# DeviceControl.net
KiCad netlist of a schematic drawn in Altium Designer
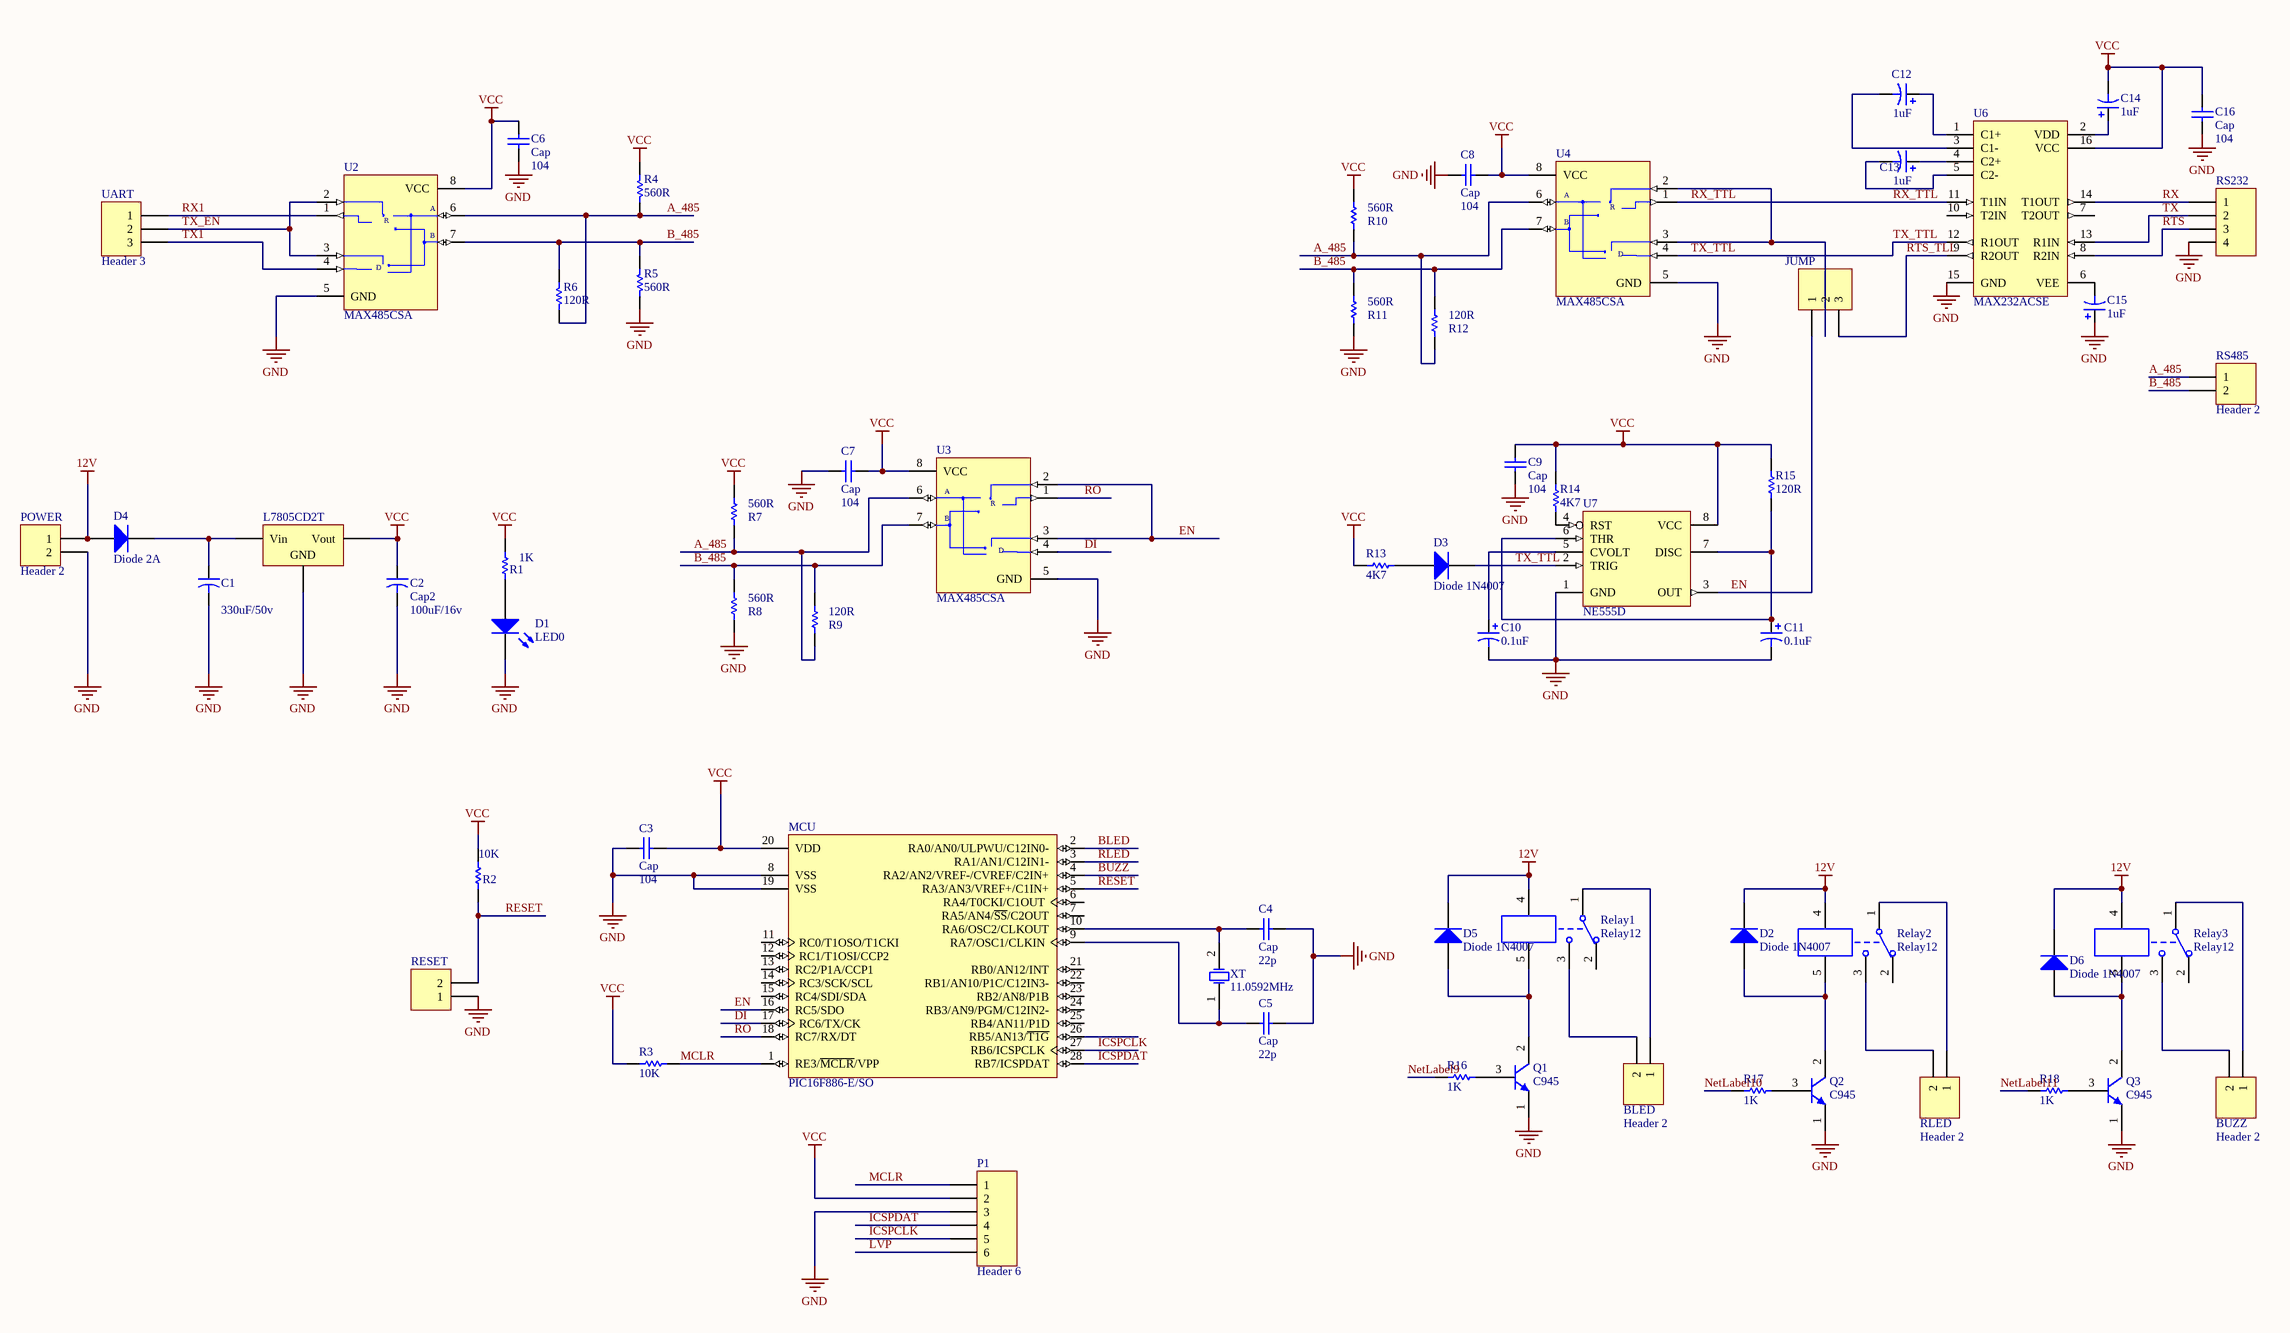
[diagram p0: DeviceControl.SchDoc]

(export (version "E")
  (design (tool "Eeschema 10.0.6"))
  (components
    (comp (ref "BLED")
      (value "Header 2")
      (footprint "Device:Header2 - duplicate")
      (description "Header, 2-Pin")
      (fields (field (name "PUBLISHER") "Altium Limited"))
      (libsource (lib "Miscellaneous Connectors") (part "Header 2"))
    )
    (comp (ref "BUZZ")
      (value "Header 2")
      (footprint "Device:Header2 - duplicate")
      (description "Header, 2-Pin")
      (fields (field (name "PUBLISHER") "Altium Limited"))
      (libsource (lib "Miscellaneous Connectors") (part "Header 2"))
    )
    (comp (ref "C1")
      (value "330uF/50v")
      (footprint "Device:TU 220uF/50V")
      (description "Capacitor")
      (fields (field (name "Comment") "Cap2") (field (name "PUBLISHER") "Altium Limited"))
      (libsource (lib "Device") (part "Cap2"))
    )
    (comp (ref "C2")
      (value "Cap2")
      (footprint "Device:tu 100uF/50v")
      (description "Capacitor")
      (fields (field (name "ALTIUM_VALUE") "100uF/16v") (field (name "PUBLISHER") "Altium Limited"))
      (libsource (lib "Device") (part "Cap2"))
    )
    (comp (ref "C3")
      (value "Cap")
      (footprint "Device:C104_YELLOW")
      (description "Capcitor")
      (fields (field (name "ALTIUM_VALUE") "104"))
      (libsource (lib "Device_Component") (part "Ceramic"))
    )
    (comp (ref "C4")
      (value "Cap")
      (footprint "Device:C104_PINK")
      (description "Capcitor")
      (fields (field (name "ALTIUM_VALUE") "22p"))
      (libsource (lib "Device_Component") (part "Ceramic"))
    )
    (comp (ref "C5")
      (value "Cap")
      (footprint "Device:C104_PINK")
      (description "Capcitor")
      (fields (field (name "ALTIUM_VALUE") "22p"))
      (libsource (lib "Device_Component") (part "Ceramic"))
    )
    (comp (ref "C6")
      (value "Cap")
      (footprint "Device:C104_PINK")
      (description "Capcitor")
      (fields (field (name "ALTIUM_VALUE") "104"))
      (libsource (lib "") (part "Ceramic_1"))
    )
    (comp (ref "C7")
      (value "Cap")
      (footprint "Device:C104_YELLOW")
      (description "Capcitor")
      (fields (field (name "ALTIUM_VALUE") "104"))
      (libsource (lib "Device_Component") (part "Ceramic"))
    )
    (comp (ref "C8")
      (value "Cap")
      (footprint "Device:C104_PINK")
      (description "Capcitor")
      (fields (field (name "ALTIUM_VALUE") "104"))
      (libsource (lib "Device_Component") (part "Ceramic"))
    )
    (comp (ref "C9")
      (value "Cap")
      (footprint "Device:C104_PINK")
      (description "Capcitor")
      (fields (field (name "ALTIUM_VALUE") "104"))
      (libsource (lib "Device_Component") (part "Ceramic"))
    )
    (comp (ref "C10")
      (value "0.1uF")
      (footprint "Device:C104_YELLOW")
      (description "Polarized Capacitor (Radial)")
      (fields (field (name "Comment") "Cap Pol1") (field (name "PUBLISHER") "Altium Limited"))
      (libsource (lib "Miscellaneous Devices") (part "Cap Pol1"))
    )
    (comp (ref "C11")
      (value "0.1uF")
      (footprint "Device:C104_YELLOW")
      (description "Polarized Capacitor (Radial)")
      (fields (field (name "Comment") "Cap Pol1") (field (name "PUBLISHER") "Altium Limited"))
      (libsource (lib "Miscellaneous Devices") (part "Cap Pol1"))
    )
    (comp (ref "C12")
      (value "1uF")
      (footprint "Device:tu 10uF")
      (description "Polarized Capacitor (Radial)")
      (fields (field (name "Comment") "Cap Pol1") (field (name "PUBLISHER") "Altium Limited"))
      (libsource (lib "Miscellaneous Devices") (part "Cap Pol1"))
    )
    (comp (ref "C13")
      (value "1uF")
      (footprint "Device:tu 10uF")
      (description "Polarized Capacitor (Radial)")
      (fields (field (name "Comment") "Cap Pol1") (field (name "PUBLISHER") "Altium Limited"))
      (libsource (lib "Miscellaneous Devices") (part "Cap Pol1"))
    )
    (comp (ref "C14")
      (value "1uF")
      (footprint "Device:tu 10uF")
      (description "Polarized Capacitor (Radial)")
      (fields (field (name "Comment") "Cap Pol1") (field (name "PUBLISHER") "Altium Limited"))
      (libsource (lib "Miscellaneous Devices") (part "Cap Pol1"))
    )
    (comp (ref "C15")
      (value "1uF")
      (footprint "Device:tu 10uF")
      (description "Polarized Capacitor (Radial)")
      (fields (field (name "Comment") "Cap Pol1") (field (name "PUBLISHER") "Altium Limited"))
      (libsource (lib "Miscellaneous Devices") (part "Cap Pol1"))
    )
    (comp (ref "C16")
      (value "Cap")
      (footprint "Device:C104_PINK")
      (description "Capcitor")
      (fields (field (name "ALTIUM_VALUE") "104"))
      (libsource (lib "Device_Component") (part "Ceramic"))
    )
    (comp (ref "D1")
      (value "LED0")
      (footprint "Device:LED_3")
      (description "Typical INFRARED GaAs LED")
      (fields (field (name "PUBLISHER") "Altium Limited"))
      (libsource (lib "Miscellaneous Devices") (part "LED0"))
    )
    (comp (ref "D2")
      (value "Diode 1N4007")
      (footprint "DIO10.46-5.3x2.8")
      (description "1 Amp General Purpose Rectifier")
      (fields (field (name "PUBLISHER") "Altium Limited"))
      (libsource (lib "Miscellaneous Devices") (part "Diode 1N4007"))
    )
    (comp (ref "D3")
      (value "Diode 1N4007")
      (footprint "Device:D_1A")
      (description "1 Amp General Purpose Rectifier")
      (fields (field (name "PUBLISHER") "Altium Limited"))
      (libsource (lib "Miscellaneous Devices") (part "Diode 1N4007"))
    )
    (comp (ref "D4")
      (value "Diode 2A")
      (footprint "Device:D_2A")
      (description "1 Amp General Purpose Rectifier")
      (fields (field (name "PUBLISHER") "Altium Limited"))
      (libsource (lib "Miscellaneous Devices") (part "Diode 1N4007"))
    )
    (comp (ref "D5")
      (value "Diode 1N4007")
      (footprint "DIO10.46-5.3x2.8")
      (description "1 Amp General Purpose Rectifier")
      (fields (field (name "PUBLISHER") "Altium Limited"))
      (libsource (lib "Miscellaneous Devices") (part "Diode 1N4007"))
    )
    (comp (ref "D6")
      (value "Diode 1N4007")
      (footprint "DIO10.46-5.3x2.8")
      (description "1 Amp General Purpose Rectifier")
      (fields (field (name "PUBLISHER") "Altium Limited"))
      (libsource (lib "Miscellaneous Devices") (part "Diode 1N4007"))
    )
    (comp (ref "JUMP")
      (value "Header 3")
      (footprint "HDR1X3")
      (description "Header, 3-Pin")
      (fields (field (name "PUBLISHER") "Altium Limited"))
      (libsource (lib "Miscellaneous Connectors") (part "Header 3"))
    )
    (comp (ref "L7805CD2T")
      (value "Volt Reg")
      (footprint "TO254P1510-3_4N")
      (description "Voltage Regulator")
      (fields (field (name "PUBLISHER") "Altium Limited"))
      (libsource (lib "Miscellaneous Devices") (part "Volt Reg"))
    )
    (comp (ref "MCU")
      (value "PIC16F886-E/SO")
      (footprint "SOIC-SO28_N")
      (fields (field (name "PUBLISHER") "Altium Limited"))
      (libsource (lib "Microchip Microcontroller 8-Bit PIC16") (part "PIC16F886-E/SO"))
    )
    (comp (ref "P1")
      (value "Header 6")
      (footprint "HDR1X6")
      (description "Header, 6-Pin")
      (fields (field (name "PUBLISHER") "Altium Limited"))
      (libsource (lib "Miscellaneous Connectors") (part "Header 6"))
    )
    (comp (ref "POWER")
      (value "Header 2")
      (footprint "Device:Header2 - duplicate")
      (description "Header, 2-Pin")
      (fields (field (name "PUBLISHER") "Altium Limited"))
      (libsource (lib "Miscellaneous Connectors") (part "Header 2"))
    )
    (comp (ref "Q1")
      (value "C945")
      (footprint "Device:C1815")
      (description "NPN General Purpose Amplifier")
      (fields (field (name "PUBLISHER") "Altium Limited"))
      (libsource (lib "Miscellaneous Devices") (part "2N3904"))
    )
    (comp (ref "Q2")
      (value "C945")
      (footprint "Device:C1815")
      (description "NPN General Purpose Amplifier")
      (fields (field (name "PUBLISHER") "Altium Limited"))
      (libsource (lib "Miscellaneous Devices") (part "2N3904"))
    )
    (comp (ref "Q3")
      (value "C945")
      (footprint "Device:C1815")
      (description "NPN General Purpose Amplifier")
      (fields (field (name "PUBLISHER") "Altium Limited"))
      (libsource (lib "Miscellaneous Devices") (part "2N3904"))
    )
    (comp (ref "R1")
      (value "1K")
      (footprint "Device:R_Nor")
      (libsource (lib "Device_Component") (part "Res"))
    )
    (comp (ref "R2")
      (value "10K")
      (footprint "Device:R_Nor")
      (libsource (lib "Device_Component") (part "Res"))
    )
    (comp (ref "R3")
      (value "10K")
      (footprint "Device:R_Nor")
      (libsource (lib "Device_Component") (part "Res"))
    )
    (comp (ref "R4")
      (value "560R")
      (footprint "Device:R_Nor")
      (libsource (lib "Device_Component") (part "Res"))
    )
    (comp (ref "R5")
      (value "560R")
      (footprint "Device:R_Nor")
      (libsource (lib "Device_Component") (part "Res"))
    )
    (comp (ref "R6")
      (value "120R")
      (footprint "Device:R_Nor")
      (libsource (lib "Device_Component") (part "Res"))
    )
    (comp (ref "R7")
      (value "560R")
      (footprint "Device:R_Nor")
      (libsource (lib "Device_Component") (part "Res"))
    )
    (comp (ref "R8")
      (value "560R")
      (footprint "Device:R_Nor")
      (libsource (lib "Device_Component") (part "Res"))
    )
    (comp (ref "R9")
      (value "120R")
      (footprint "Device:R_Nor")
      (libsource (lib "Device_Component") (part "Res"))
    )
    (comp (ref "R10")
      (value "560R")
      (footprint "Device:R_Nor")
      (libsource (lib "Device_Component") (part "Res"))
    )
    (comp (ref "R11")
      (value "560R")
      (footprint "Device:R_Nor")
      (libsource (lib "Device_Component") (part "Res"))
    )
    (comp (ref "R12")
      (value "120R")
      (footprint "Device:R_Nor")
      (libsource (lib "Device_Component") (part "Res"))
    )
    (comp (ref "R13")
      (value "4K7")
      (footprint "Device:R_Nor")
      (libsource (lib "Device_Component") (part "Res"))
    )
    (comp (ref "R14")
      (value "4K7")
      (footprint "Device:R_Nor")
      (libsource (lib "Device_Component") (part "Res"))
    )
    (comp (ref "R15")
      (value "120R")
      (footprint "Device:R_Nor")
      (libsource (lib "Device_Component") (part "Res"))
    )
    (comp (ref "R16")
      (value "1K")
      (footprint "Device:R_Nor")
      (libsource (lib "Device_Component") (part "Res"))
    )
    (comp (ref "R17")
      (value "1K")
      (footprint "Device:R_Nor")
      (libsource (lib "Device_Component") (part "Res"))
    )
    (comp (ref "R18")
      (value "1K")
      (footprint "Device:R_Nor")
      (libsource (lib "Device_Component") (part "Res"))
    )
    (comp (ref "Relay1")
      (value "Relay12")
      (footprint "Device:Role 12V")
      (libsource (lib "Device") (part "Role_12V"))
    )
    (comp (ref "Relay2")
      (value "Relay12")
      (footprint "Device:Role 12V")
      (libsource (lib "Device") (part "Role_12V"))
    )
    (comp (ref "Relay3")
      (value "Relay12")
      (footprint "Device:Role 12V")
      (libsource (lib "Device") (part "Role_12V"))
    )
    (comp (ref "RESET")
      (value "Header 2")
      (footprint "Device:Header2 - duplicate")
      (description "Header, 2-Pin")
      (fields (field (name "PUBLISHER") "Altium Limited"))
      (libsource (lib "") (part "Header 2_2"))
    )
    (comp (ref "RLED")
      (value "Header 2")
      (footprint "Device:Header2 - duplicate")
      (description "Header, 2-Pin")
      (fields (field (name "PUBLISHER") "Altium Limited"))
      (libsource (lib "Miscellaneous Connectors") (part "Header 2"))
    )
    (comp (ref "RS232")
      (value "Header 4")
      (footprint "HDR1X4")
      (description "Header, 4-Pin")
      (fields (field (name "PUBLISHER") "Altium Limited"))
      (libsource (lib "Miscellaneous Connectors") (part "Header 4"))
    )
    (comp (ref "RS485")
      (value "Header 2")
      (footprint "HDR1X2")
      (description "Header, 2-Pin")
      (fields (field (name "PUBLISHER") "Altium Limited"))
      (libsource (lib "") (part "Header 2_1"))
    )
    (comp (ref "U2")
      (value "MAX485CSA")
      (footprint "NSO8_N")
      (description "Low-Power, Slew-Rate-Limited RS-485/RS-422 Transceiver")
      (fields (field (name "PUBLISHER") "Altium Limited"))
      (libsource (lib "Maxim Communication Transceiver") (part "MAX485CSA"))
    )
    (comp (ref "U3")
      (value "MAX485CSA")
      (footprint "NSO8_N")
      (description "Low-Power, Slew-Rate-Limited RS-485/RS-422 Transceiver")
      (fields (field (name "PUBLISHER") "Altium Limited"))
      (libsource (lib "") (part "MAX485CSA_1"))
    )
    (comp (ref "U4")
      (value "MAX485CSA")
      (footprint "NSO8_N")
      (description "Low-Power, Slew-Rate-Limited RS-485/RS-422 Transceiver")
      (fields (field (name "PUBLISHER") "Altium Limited"))
      (libsource (lib "") (part "MAX485CSA_1"))
    )
    (comp (ref "U6")
      (value "MAX232ACSE")
      (footprint "NSO16_N")
      (description "+5V Powered, Multi-Channel RS-232 Driver/Receiver")
      (fields (field (name "PUBLISHER") "Altium Limited"))
      (libsource (lib "Maxim Communication Transceiver") (part "MAX232ACSE"))
    )
    (comp (ref "U7")
      (value "NE555D")
      (footprint "D008_N")
      (description "Precision Timer")
      (fields (field (name "PUBLISHER") "Altium Limited"))
      (libsource (lib "TI Analog Timer Circuit") (part "NE555D"))
    )
    (comp (ref "UART")
      (value "Header 3")
      (footprint "HDR1X3")
      (description "Header, 3-Pin")
      (fields (field (name "PUBLISHER") "Altium Limited"))
      (libsource (lib "") (part "Header 3_1"))
    )
    (comp (ref "XT")
      (value "11.0592MHz")
      (footprint "Device:Xtal12M")
      (description "Crystal Oscillator")
      (fields (field (name "Comment") "XTAL") (field (name "PUBLISHER") "Altium Limited"))
      (libsource (lib "Miscellaneous Devices") (part "XTAL"))
    )
  )
  (nets
    (net (code "1") (name "/A_485") (class "Default")
      (node (ref "R10") (pin "1") (pinfunction "1_1") (pintype "passive"))
      (node (ref "R12") (pin "1") (pinfunction "1_1") (pintype "passive"))
      (node (ref "R4") (pin "1") (pinfunction "1_1") (pintype "passive"))
      (node (ref "R6") (pin "1") (pinfunction "1_1") (pintype "passive"))
      (node (ref "R7") (pin "1") (pinfunction "1_1") (pintype "passive"))
      (node (ref "R9") (pin "1") (pinfunction "1_1") (pintype "passive"))
      (node (ref "RS485") (pin "1") (pinfunction "1_1") (pintype "passive"))
      (node (ref "U2") (pin "6") (pinfunction "A_6") (pintype "bidirectional"))
      (node (ref "U3") (pin "6") (pinfunction "A_6") (pintype "bidirectional"))
      (node (ref "U4") (pin "6") (pinfunction "A_6") (pintype "bidirectional"))
    )
    (net (code "2") (name "/BLED") (class "Default")
      (node (ref "MCU") (pin "2") (pinfunction "RA0/AN0/ULPWU/C12IN0-_2") (pintype "bidirectional"))
    )
    (net (code "3") (name "/BUZZ") (class "Default")
      (node (ref "MCU") (pin "4") (pinfunction "RA2/AN2/VREF-/CVREF/C2IN+_4") (pintype "bidirectional"))
    )
    (net (code "4") (name "/B_485") (class "Default")
      (node (ref "R11") (pin "2") (pinfunction "2_2") (pintype "passive"))
      (node (ref "R12") (pin "2") (pinfunction "2_2") (pintype "passive"))
      (node (ref "R5") (pin "2") (pinfunction "2_2") (pintype "passive"))
      (node (ref "R6") (pin "2") (pinfunction "2_2") (pintype "passive"))
      (node (ref "R8") (pin "2") (pinfunction "2_2") (pintype "passive"))
      (node (ref "R9") (pin "2") (pinfunction "2_2") (pintype "passive"))
      (node (ref "RS485") (pin "2") (pinfunction "2_2") (pintype "passive"))
      (node (ref "U2") (pin "7") (pinfunction "B_7") (pintype "bidirectional"))
      (node (ref "U3") (pin "7") (pinfunction "B_7") (pintype "bidirectional"))
      (node (ref "U4") (pin "7") (pinfunction "B_7") (pintype "bidirectional"))
    )
    (net (code "5") (name "/DI") (class "Default")
      (node (ref "MCU") (pin "17") (pinfunction "RC6/TX/CK_17") (pintype "bidirectional"))
      (node (ref "U3") (pin "4") (pinfunction "DI_4") (pintype "input"))
    )
    (net (code "6") (name "/EN") (class "Default")
      (node (ref "JUMP") (pin "1") (pinfunction "1_1") (pintype "passive"))
      (node (ref "MCU") (pin "16") (pinfunction "RC5/SDO_16") (pintype "bidirectional"))
      (node (ref "U3") (pin "2") (pinfunction "~{RE}_2") (pintype "input"))
      (node (ref "U3") (pin "3") (pinfunction "DE_3") (pintype "input"))
      (node (ref "U7") (pin "3") (pinfunction "OUT_3") (pintype "output"))
    )
    (net (code "7") (name "/ICSPCLK") (class "Default")
      (node (ref "MCU") (pin "27") (pinfunction "RB6/ICSPCLK_27") (pintype "bidirectional"))
      (node (ref "P1") (pin "5") (pinfunction "5_5") (pintype "passive"))
    )
    (net (code "8") (name "/ICSPDAT") (class "Default")
      (node (ref "MCU") (pin "28") (pinfunction "RB7/ICSPDAT_28") (pintype "bidirectional"))
      (node (ref "P1") (pin "4") (pinfunction "4_4") (pintype "passive"))
    )
    (net (code "9") (name "/LVP") (class "Default")
      (node (ref "P1") (pin "6") (pinfunction "6_6") (pintype "passive"))
    )
    (net (code "10") (name "/MCLR") (class "Default")
      (node (ref "MCU") (pin "1") (pinfunction "RE3/~{MCLR}/VPP_1") (pintype "bidirectional"))
      (node (ref "P1") (pin "1") (pinfunction "1_1") (pintype "passive"))
      (node (ref "R3") (pin "1") (pinfunction "1_1") (pintype "passive"))
    )
    (net (code "11") (name "/NetLabel9") (class "Default")
      (node (ref "R16") (pin "2") (pinfunction "2_2") (pintype "passive"))
    )
    (net (code "12") (name "/NetLabel10") (class "Default")
      (node (ref "R17") (pin "2") (pinfunction "2_2") (pintype "passive"))
    )
    (net (code "13") (name "/NetLabel11") (class "Default")
      (node (ref "R18") (pin "2") (pinfunction "2_2") (pintype "passive"))
    )
    (net (code "14") (name "/RESET") (class "Default")
      (node (ref "MCU") (pin "5") (pinfunction "RA3/AN3/VREF+/C1IN+_5") (pintype "bidirectional"))
      (node (ref "R2") (pin "1") (pinfunction "1_1") (pintype "passive"))
      (node (ref "RESET") (pin "2") (pinfunction "2_2") (pintype "passive"))
    )
    (net (code "15") (name "/RLED") (class "Default")
      (node (ref "MCU") (pin "3") (pinfunction "RA1/AN1/C12IN1-_3") (pintype "bidirectional"))
    )
    (net (code "16") (name "/RO") (class "Default")
      (node (ref "MCU") (pin "18") (pinfunction "RC7/RX/DT_18") (pintype "bidirectional"))
      (node (ref "U3") (pin "1") (pinfunction "RO_1") (pintype "output"))
    )
    (net (code "17") (name "/RTS") (class "Default")
      (node (ref "RS232") (pin "3") (pinfunction "3_3") (pintype "passive"))
      (node (ref "U6") (pin "8") (pinfunction "R2IN_8") (pintype "input"))
    )
    (net (code "18") (name "/RTS_TLL") (class "Default")
      (node (ref "JUMP") (pin "3") (pinfunction "3_3") (pintype "passive"))
      (node (ref "U6") (pin "9") (pinfunction "R2OUT_9") (pintype "output"))
    )
    (net (code "19") (name "/RX") (class "Default")
      (node (ref "RS232") (pin "1") (pinfunction "1_1") (pintype "passive"))
      (node (ref "U6") (pin "14") (pinfunction "T1OUT_14") (pintype "output"))
    )
    (net (code "20") (name "/RX1") (class "Default")
      (node (ref "U2") (pin "1") (pinfunction "RO_1") (pintype "output"))
      (node (ref "UART") (pin "1") (pinfunction "1_1") (pintype "passive"))
    )
    (net (code "21") (name "/RX_TTL") (class "Default")
      (node (ref "U4") (pin "1") (pinfunction "RO_1") (pintype "output"))
      (node (ref "U6") (pin "11") (pinfunction "T1IN_11") (pintype "input"))
    )
    (net (code "22") (name "/TX") (class "Default")
      (node (ref "RS232") (pin "2") (pinfunction "2_2") (pintype "passive"))
      (node (ref "U6") (pin "13") (pinfunction "R1IN_13") (pintype "input"))
    )
    (net (code "23") (name "/TX1") (class "Default")
      (node (ref "U2") (pin "4") (pinfunction "DI_4") (pintype "input"))
      (node (ref "UART") (pin "3") (pinfunction "3_3") (pintype "passive"))
    )
    (net (code "24") (name "/TX_EN") (class "Default")
      (node (ref "U2") (pin "2") (pinfunction "~{RE}_2") (pintype "input"))
      (node (ref "U2") (pin "3") (pinfunction "DE_3") (pintype "input"))
      (node (ref "UART") (pin "2") (pinfunction "2_2") (pintype "passive"))
    )
    (net (code "25") (name "/TX_TTL") (class "Default")
      (node (ref "D3") (pin "2") (pinfunction "K_2") (pintype "passive"))
      (node (ref "U4") (pin "4") (pinfunction "DI_4") (pintype "input"))
      (node (ref "U6") (pin "12") (pinfunction "R1OUT_12") (pintype "output"))
      (node (ref "U7") (pin "2") (pinfunction "TRIG_2") (pintype "input"))
    )
    (net (code "26") (name "12V") (class "Default")
      (node (ref "D2") (pin "2") (pinfunction "K_2") (pintype "passive"))
      (node (ref "D4") (pin "1") (pinfunction "A_1") (pintype "passive"))
      (node (ref "D5") (pin "2") (pinfunction "K_2") (pintype "passive"))
      (node (ref "D6") (pin "2") (pinfunction "K_2") (pintype "passive"))
      (node (ref "POWER") (pin "1") (pinfunction "1_1") (pintype "passive"))
      (node (ref "Relay1") (pin "4") (pinfunction "4_4") (pintype "passive"))
      (node (ref "Relay2") (pin "4") (pinfunction "4_4") (pintype "passive"))
      (node (ref "Relay3") (pin "4") (pinfunction "4_4") (pintype "passive"))
    )
    (net (code "27") (name "GND") (class "Default")
      (node (ref "C1") (pin "2") (pinfunction "2_2") (pintype "passive"))
      (node (ref "C10") (pin "2") (pinfunction "2_2") (pintype "passive"))
      (node (ref "C11") (pin "2") (pinfunction "2_2") (pintype "passive"))
      (node (ref "C15") (pin "1") (pinfunction "1_1") (pintype "passive"))
      (node (ref "C16") (pin "1") (pinfunction "1_1") (pintype "passive"))
      (node (ref "C2") (pin "2") (pinfunction "2_2") (pintype "passive"))
      (node (ref "C3") (pin "2") (pinfunction "2_2") (pintype "passive"))
      (node (ref "C4") (pin "2") (pinfunction "2_2") (pintype "passive"))
      (node (ref "C5") (pin "2") (pinfunction "2_2") (pintype "passive"))
      (node (ref "C6") (pin "2") (pinfunction "2_2") (pintype "passive"))
      (node (ref "C7") (pin "1") (pinfunction "1_1") (pintype "passive"))
      (node (ref "C8") (pin "1") (pinfunction "1_1") (pintype "passive"))
      (node (ref "C9") (pin "1") (pinfunction "1_1") (pintype "passive"))
      (node (ref "D1") (pin "2") (pinfunction "K_2") (pintype "passive"))
      (node (ref "L7805CD2T") (pin "2") (pinfunction "GND_2") (pintype "passive"))
      (node (ref "MCU") (pin "19") (pinfunction "VSS_19") (pintype "power_in"))
      (node (ref "MCU") (pin "8") (pinfunction "VSS_8") (pintype "power_in"))
      (node (ref "P1") (pin "3") (pinfunction "3_3") (pintype "passive"))
      (node (ref "POWER") (pin "2") (pinfunction "2_2") (pintype "passive"))
      (node (ref "Q1") (pin "1") (pinfunction "E_1") (pintype "passive"))
      (node (ref "Q2") (pin "1") (pinfunction "E_1") (pintype "passive"))
      (node (ref "Q3") (pin "1") (pinfunction "E_1") (pintype "passive"))
      (node (ref "R11") (pin "1") (pinfunction "1_1") (pintype "passive"))
      (node (ref "R5") (pin "1") (pinfunction "1_1") (pintype "passive"))
      (node (ref "R8") (pin "1") (pinfunction "1_1") (pintype "passive"))
      (node (ref "RESET") (pin "1") (pinfunction "1_1") (pintype "passive"))
      (node (ref "RS232") (pin "4") (pinfunction "4_4") (pintype "passive"))
      (node (ref "U2") (pin "5") (pinfunction "GND_5") (pintype "power_in"))
      (node (ref "U3") (pin "5") (pinfunction "GND_5") (pintype "power_in"))
      (node (ref "U4") (pin "5") (pinfunction "GND_5") (pintype "power_in"))
      (node (ref "U6") (pin "15") (pinfunction "GND_15") (pintype "power_in"))
      (node (ref "U7") (pin "1") (pinfunction "GND_1") (pintype "power_in"))
    )
    (net (code "28") (name "Net-(BLED-Pad1)") (class "Default")
      (node (ref "BLED") (pin "1") (pinfunction "1_1") (pintype "passive"))
      (node (ref "Relay1") (pin "1") (pinfunction "1_1") (pintype "passive"))
    )
    (net (code "29") (name "Net-(BLED-Pad2)") (class "Default")
      (node (ref "BLED") (pin "2") (pinfunction "2_2") (pintype "passive"))
      (node (ref "Relay1") (pin "3") (pinfunction "3_3") (pintype "passive"))
    )
    (net (code "30") (name "Net-(BUZZ-Pad1)") (class "Default")
      (node (ref "BUZZ") (pin "1") (pinfunction "1_1") (pintype "passive"))
      (node (ref "Relay3") (pin "1") (pinfunction "1_1") (pintype "passive"))
    )
    (net (code "31") (name "Net-(BUZZ-Pad2)") (class "Default")
      (node (ref "BUZZ") (pin "2") (pinfunction "2_2") (pintype "passive"))
      (node (ref "Relay3") (pin "3") (pinfunction "3_3") (pintype "passive"))
    )
    (net (code "32") (name "Net-(D1-A)") (class "Default")
      (node (ref "D1") (pin "1") (pinfunction "A_1") (pintype "passive"))
      (node (ref "R1") (pin "1") (pinfunction "1_1") (pintype "passive"))
    )
    (net (code "33") (name "Net-(D2-A)") (class "Default")
      (node (ref "D2") (pin "1") (pinfunction "A_1") (pintype "passive"))
      (node (ref "Q2") (pin "2") (pinfunction "C_2") (pintype "passive"))
      (node (ref "Relay2") (pin "5") (pinfunction "5_5") (pintype "passive"))
    )
    (net (code "34") (name "Net-(D3-A)") (class "Default")
      (node (ref "D3") (pin "1") (pinfunction "A_1") (pintype "passive"))
      (node (ref "R13") (pin "1") (pinfunction "1_1") (pintype "passive"))
    )
    (net (code "35") (name "Net-(D4-K)") (class "Default")
      (node (ref "C1") (pin "1") (pinfunction "1_1") (pintype "passive"))
      (node (ref "D4") (pin "2") (pinfunction "K_2") (pintype "passive"))
      (node (ref "L7805CD2T") (pin "1") (pinfunction "Vin_1") (pintype "passive"))
    )
    (net (code "36") (name "Net-(D5-A)") (class "Default")
      (node (ref "D5") (pin "1") (pinfunction "A_1") (pintype "passive"))
      (node (ref "Q1") (pin "2") (pinfunction "C_2") (pintype "passive"))
      (node (ref "Relay1") (pin "5") (pinfunction "5_5") (pintype "passive"))
    )
    (net (code "37") (name "Net-(D6-A)") (class "Default")
      (node (ref "D6") (pin "1") (pinfunction "A_1") (pintype "passive"))
      (node (ref "Q3") (pin "2") (pinfunction "C_2") (pintype "passive"))
      (node (ref "Relay3") (pin "5") (pinfunction "5_5") (pintype "passive"))
    )
    (net (code "38") (name "Net-(MCU-RA6{slash}OSC2{slash}CLKOUT)") (class "Default")
      (node (ref "C4") (pin "1") (pinfunction "1_1") (pintype "passive"))
      (node (ref "MCU") (pin "10") (pinfunction "RA6/OSC2/CLKOUT_10") (pintype "bidirectional"))
      (node (ref "XT") (pin "2") (pinfunction "OSC2_2") (pintype "passive"))
    )
    (net (code "39") (name "Net-(MCU-RA7{slash}OSC1{slash}CLKIN)") (class "Default")
      (node (ref "C5") (pin "1") (pinfunction "1_1") (pintype "passive"))
      (node (ref "MCU") (pin "9") (pinfunction "RA7/OSC1/CLKIN_9") (pintype "bidirectional"))
      (node (ref "XT") (pin "1") (pinfunction "OSC1_1") (pintype "passive"))
    )
    (net (code "40") (name "Net-(Q1-B)") (class "Default")
      (node (ref "Q1") (pin "3") (pinfunction "B_3") (pintype "passive"))
      (node (ref "R16") (pin "1") (pinfunction "1_1") (pintype "passive"))
    )
    (net (code "41") (name "Net-(Q2-B)") (class "Default")
      (node (ref "Q2") (pin "3") (pinfunction "B_3") (pintype "passive"))
      (node (ref "R17") (pin "1") (pinfunction "1_1") (pintype "passive"))
    )
    (net (code "42") (name "Net-(Q3-B)") (class "Default")
      (node (ref "Q3") (pin "3") (pinfunction "B_3") (pintype "passive"))
      (node (ref "R18") (pin "1") (pinfunction "1_1") (pintype "passive"))
    )
    (net (code "43") (name "Net-(RLED-Pad1)") (class "Default")
      (node (ref "RLED") (pin "1") (pinfunction "1_1") (pintype "passive"))
      (node (ref "Relay2") (pin "1") (pinfunction "1_1") (pintype "passive"))
    )
    (net (code "44") (name "Net-(RLED-Pad2)") (class "Default")
      (node (ref "RLED") (pin "2") (pinfunction "2_2") (pintype "passive"))
      (node (ref "Relay2") (pin "3") (pinfunction "3_3") (pintype "passive"))
    )
    (net (code "45") (name "Net-(U4-DE)") (class "Default")
      (node (ref "JUMP") (pin "2") (pinfunction "2_2") (pintype "passive"))
      (node (ref "U4") (pin "2") (pinfunction "~{RE}_2") (pintype "input"))
      (node (ref "U4") (pin "3") (pinfunction "DE_3") (pintype "input"))
    )
    (net (code "46") (name "Net-(U6-C1+)") (class "Default")
      (node (ref "C12") (pin "1") (pinfunction "1_1") (pintype "passive"))
      (node (ref "U6") (pin "1") (pinfunction "C1+_1") (pintype "passive"))
    )
    (net (code "47") (name "Net-(U6-C1-)") (class "Default")
      (node (ref "C12") (pin "2") (pinfunction "2_2") (pintype "passive"))
      (node (ref "U6") (pin "3") (pinfunction "C1-_3") (pintype "passive"))
    )
    (net (code "48") (name "Net-(U6-C2+)") (class "Default")
      (node (ref "C13") (pin "1") (pinfunction "1_1") (pintype "passive"))
      (node (ref "U6") (pin "4") (pinfunction "C2+_4") (pintype "passive"))
    )
    (net (code "49") (name "Net-(U6-C2-)") (class "Default")
      (node (ref "C13") (pin "2") (pinfunction "2_2") (pintype "passive"))
      (node (ref "U6") (pin "5") (pinfunction "C2-_5") (pintype "passive"))
    )
    (net (code "50") (name "Net-(U6-VDD)") (class "Default")
      (node (ref "C14") (pin "1") (pinfunction "1_1") (pintype "passive"))
      (node (ref "U6") (pin "2") (pinfunction "VDD_2") (pintype "power_in"))
    )
    (net (code "51") (name "Net-(U6-VEE)") (class "Default")
      (node (ref "C15") (pin "2") (pinfunction "2_2") (pintype "passive"))
      (node (ref "U6") (pin "6") (pinfunction "VEE_6") (pintype "power_in"))
    )
    (net (code "52") (name "Net-(U7-CVOLT)") (class "Default")
      (node (ref "C10") (pin "1") (pinfunction "1_1") (pintype "passive"))
      (node (ref "U7") (pin "5") (pinfunction "CVOLT_5") (pintype "passive"))
    )
    (net (code "53") (name "Net-(U7-DISC)") (class "Default")
      (node (ref "C11") (pin "1") (pinfunction "1_1") (pintype "passive"))
      (node (ref "R15") (pin "2") (pinfunction "2_2") (pintype "passive"))
      (node (ref "U7") (pin "6") (pinfunction "THR_6") (pintype "input"))
      (node (ref "U7") (pin "7") (pinfunction "DISC_7") (pintype "open_collector"))
    )
    (net (code "54") (name "Net-(U7-RST)") (class "Default")
      (node (ref "R14") (pin "2") (pinfunction "2_2") (pintype "passive"))
      (node (ref "U7") (pin "4") (pinfunction "RST_4") (pintype "input"))
    )
    (net (code "55") (name "VCC") (class "Default")
      (node (ref "C14") (pin "2") (pinfunction "2_2") (pintype "passive"))
      (node (ref "C16") (pin "2") (pinfunction "2_2") (pintype "passive"))
      (node (ref "C2") (pin "1") (pinfunction "1_1") (pintype "passive"))
      (node (ref "C3") (pin "1") (pinfunction "1_1") (pintype "passive"))
      (node (ref "C6") (pin "1") (pinfunction "1_1") (pintype "passive"))
      (node (ref "C7") (pin "2") (pinfunction "2_2") (pintype "passive"))
      (node (ref "C8") (pin "2") (pinfunction "2_2") (pintype "passive"))
      (node (ref "C9") (pin "2") (pinfunction "2_2") (pintype "passive"))
      (node (ref "L7805CD2T") (pin "3") (pinfunction "Vout_3") (pintype "passive"))
      (node (ref "MCU") (pin "20") (pinfunction "VDD_20") (pintype "power_in"))
      (node (ref "P1") (pin "2") (pinfunction "2_2") (pintype "passive"))
      (node (ref "R1") (pin "2") (pinfunction "2_2") (pintype "passive"))
      (node (ref "R10") (pin "2") (pinfunction "2_2") (pintype "passive"))
      (node (ref "R13") (pin "2") (pinfunction "2_2") (pintype "passive"))
      (node (ref "R14") (pin "1") (pinfunction "1_1") (pintype "passive"))
      (node (ref "R15") (pin "1") (pinfunction "1_1") (pintype "passive"))
      (node (ref "R2") (pin "2") (pinfunction "2_2") (pintype "passive"))
      (node (ref "R3") (pin "2") (pinfunction "2_2") (pintype "passive"))
      (node (ref "R4") (pin "2") (pinfunction "2_2") (pintype "passive"))
      (node (ref "R7") (pin "2") (pinfunction "2_2") (pintype "passive"))
      (node (ref "U2") (pin "8") (pinfunction "VCC_8") (pintype "power_in"))
      (node (ref "U3") (pin "8") (pinfunction "VCC_8") (pintype "power_in"))
      (node (ref "U4") (pin "8") (pinfunction "VCC_8") (pintype "power_in"))
      (node (ref "U6") (pin "16") (pinfunction "VCC_16") (pintype "power_in"))
      (node (ref "U7") (pin "8") (pinfunction "VCC_8") (pintype "power_in"))
    )
    (net (code "56") (name "unconnected-(MCU-RA4{slash}T0CKI{slash}C1OUT-Pad6)") (class "Default")
      (node (ref "MCU") (pin "6") (pinfunction "RA4/T0CKI/C1OUT_6") (pintype "bidirectional"))
    )
    (net (code "57") (name "unconnected-(MCU-RA5{slash}AN4{slash}~{SS}{slash}C2OUT-Pad7)") (class "Default")
      (node (ref "MCU") (pin "7") (pinfunction "RA5/AN4/~{SS}/C2OUT_7") (pintype "bidirectional"))
    )
    (net (code "58") (name "unconnected-(MCU-RB0{slash}AN12{slash}INT-Pad21)") (class "Default")
      (node (ref "MCU") (pin "21") (pinfunction "RB0/AN12/INT_21") (pintype "bidirectional"))
    )
    (net (code "59") (name "unconnected-(MCU-RB1{slash}AN10{slash}P1C{slash}C12IN3--Pad22)") (class "Default")
      (node (ref "MCU") (pin "22") (pinfunction "RB1/AN10/P1C/C12IN3-_22") (pintype "bidirectional"))
    )
    (net (code "60") (name "unconnected-(MCU-RB2{slash}AN8{slash}P1B-Pad23)") (class "Default")
      (node (ref "MCU") (pin "23") (pinfunction "RB2/AN8/P1B_23") (pintype "bidirectional"))
    )
    (net (code "61") (name "unconnected-(MCU-RB3{slash}AN9{slash}PGM{slash}C12IN2--Pad24)") (class "Default")
      (node (ref "MCU") (pin "24") (pinfunction "RB3/AN9/PGM/C12IN2-_24") (pintype "bidirectional"))
    )
    (net (code "62") (name "unconnected-(MCU-RB4{slash}AN11{slash}P1D-Pad25)") (class "Default")
      (node (ref "MCU") (pin "25") (pinfunction "RB4/AN11/P1D_25") (pintype "bidirectional"))
    )
    (net (code "63") (name "unconnected-(MCU-RB5{slash}AN13{slash}~{T1G}-Pad26)") (class "Default")
      (node (ref "MCU") (pin "26") (pinfunction "RB5/AN13/~{T1G}_26") (pintype "bidirectional"))
    )
    (net (code "64") (name "unconnected-(MCU-RC0{slash}T1OSO{slash}T1CKI-Pad11)") (class "Default")
      (node (ref "MCU") (pin "11") (pinfunction "RC0/T1OSO/T1CKI_11") (pintype "bidirectional"))
    )
    (net (code "65") (name "unconnected-(MCU-RC1{slash}T1OSI{slash}CCP2-Pad12)") (class "Default")
      (node (ref "MCU") (pin "12") (pinfunction "RC1/T1OSI/CCP2_12") (pintype "bidirectional"))
    )
    (net (code "66") (name "unconnected-(MCU-RC2{slash}P1A{slash}CCP1-Pad13)") (class "Default")
      (node (ref "MCU") (pin "13") (pinfunction "RC2/P1A/CCP1_13") (pintype "bidirectional"))
    )
    (net (code "67") (name "unconnected-(MCU-RC3{slash}SCK{slash}SCL-Pad14)") (class "Default")
      (node (ref "MCU") (pin "14") (pinfunction "RC3/SCK/SCL_14") (pintype "bidirectional"))
    )
    (net (code "68") (name "unconnected-(MCU-RC4{slash}SDI{slash}SDA-Pad15)") (class "Default")
      (node (ref "MCU") (pin "15") (pinfunction "RC4/SDI/SDA_15") (pintype "bidirectional"))
    )
    (net (code "69") (name "unconnected-(Relay1-Pad2)") (class "Default")
      (node (ref "Relay1") (pin "2") (pinfunction "2_2") (pintype "passive"))
    )
    (net (code "70") (name "unconnected-(Relay2-Pad2)") (class "Default")
      (node (ref "Relay2") (pin "2") (pinfunction "2_2") (pintype "passive"))
    )
    (net (code "71") (name "unconnected-(Relay3-Pad2)") (class "Default")
      (node (ref "Relay3") (pin "2") (pinfunction "2_2") (pintype "passive"))
    )
    (net (code "72") (name "unconnected-(U6-T2IN-Pad10)") (class "Default")
      (node (ref "U6") (pin "10") (pinfunction "T2IN_10") (pintype "input"))
    )
    (net (code "73") (name "unconnected-(U6-T2OUT-Pad7)") (class "Default")
      (node (ref "U6") (pin "7") (pinfunction "T2OUT_7") (pintype "output"))
    )
  )
)
